# WL-BPF.net
KiCad netlist of a schematic drawn in Altium Designer
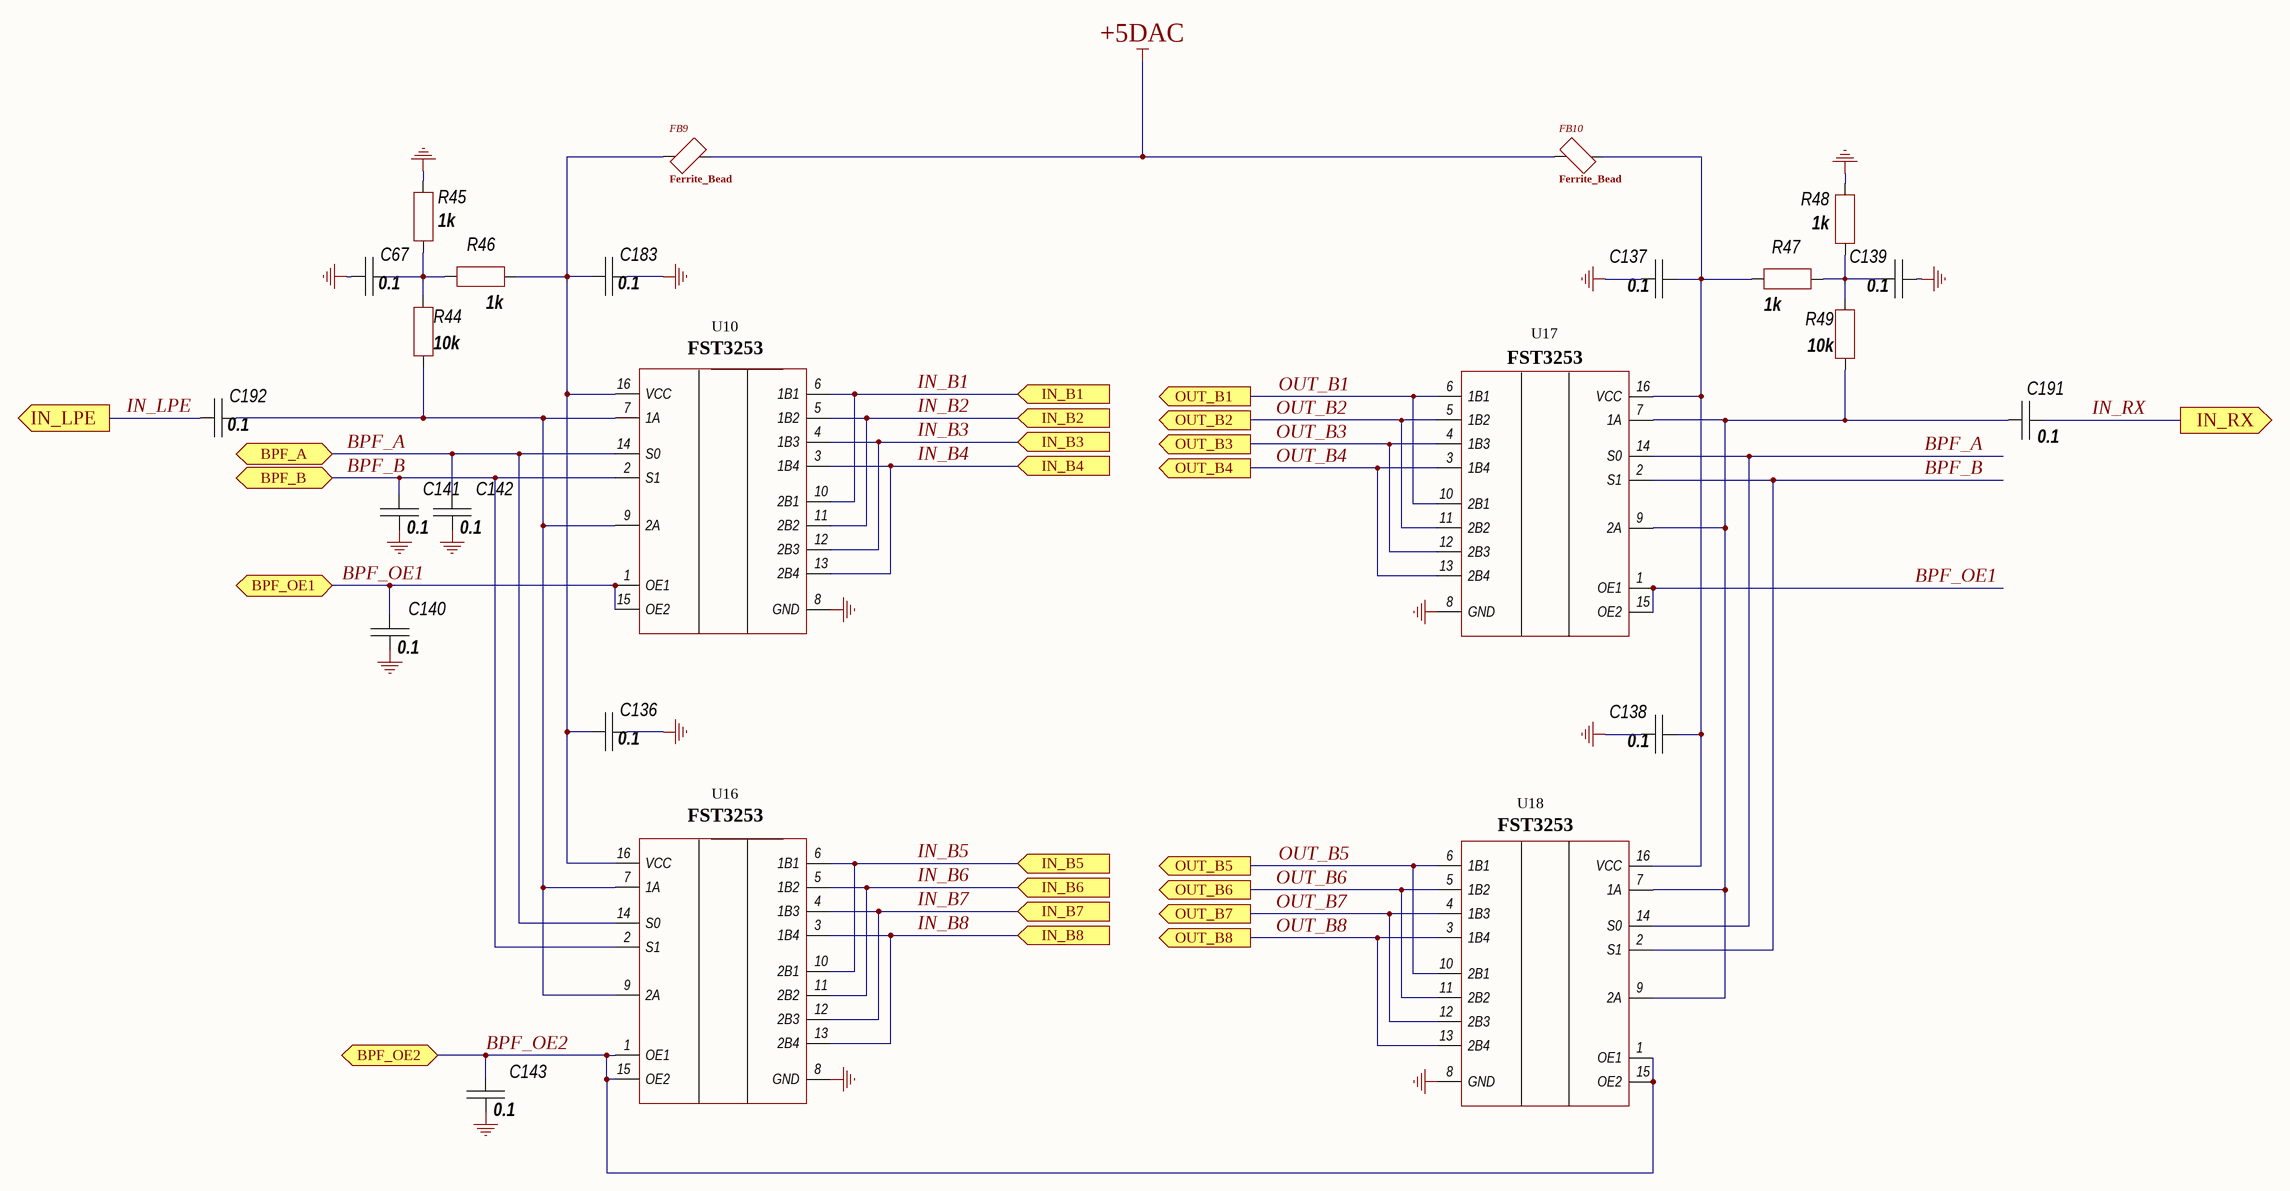
[diagram p0: WL-BPF.SchDoc]

(export (version "E")
  (design (tool "Eeschema 10.0.6"))
  (components
    (comp (ref "C67")
      (value "0.1")
      (footprint "standard:CH0805C")
      (libsource (lib "Discrete") (part "Capacitor"))
    )
    (comp (ref "C136")
      (value "0.1")
      (footprint "standard:CH0805C")
      (libsource (lib "Discrete") (part "Capacitor"))
    )
    (comp (ref "C137")
      (value "0.1")
      (footprint "standard:CH0805C")
      (libsource (lib "Discrete") (part "Capacitor"))
    )
    (comp (ref "C138")
      (value "0.1")
      (footprint "standard:CH0805C")
      (libsource (lib "Discrete") (part "Capacitor"))
    )
    (comp (ref "C139")
      (value "0.1")
      (footprint "standard:CH0805C")
      (libsource (lib "Discrete") (part "Capacitor"))
    )
    (comp (ref "C140")
      (value "0.1")
      (footprint "standard:CH0805C")
      (libsource (lib "Discrete") (part "Capacitor"))
    )
    (comp (ref "C141")
      (value "0.1")
      (footprint "standard:CH0805C")
      (libsource (lib "Discrete") (part "Capacitor"))
    )
    (comp (ref "C142")
      (value "0.1")
      (footprint "standard:CH0805C")
      (libsource (lib "Discrete") (part "Capacitor"))
    )
    (comp (ref "C143")
      (value "0.1")
      (footprint "standard:CH0805C")
      (libsource (lib "Discrete") (part "Capacitor"))
    )
    (comp (ref "C183")
      (value "0.1")
      (footprint "standard:CH0805C")
      (libsource (lib "Discrete") (part "Capacitor"))
    )
    (comp (ref "C191")
      (value "0.1")
      (footprint "standard:CH0805C")
      (libsource (lib "Discrete") (part "Capacitor"))
    )
    (comp (ref "C192")
      (value "0.1")
      (footprint "standard:CH0805C")
      (libsource (lib "Discrete") (part "Capacitor"))
    )
    (comp (ref "FB9") (value "Ferrite_Bead") (footprint "CH0805L") (libsource (lib "Discrete") (part "FB")))
    (comp (ref "FB10") (value "Ferrite_Bead") (footprint "CH0805L") (libsource (lib "Discrete") (part "FB")))
    (comp (ref "R44")
      (value "10k")
      (footprint "standard:CH0805R")
      (libsource (lib "Discrete") (part "Resistor"))
    )
    (comp (ref "R45") (value "1k") (footprint "standard:CH0805R") (libsource (lib "") (part "Resistor_2")))
    (comp (ref "R46") (value "1k") (footprint "standard:CH0805R") (libsource (lib "") (part "Resistor_1")))
    (comp (ref "R47")
      (value "1k")
      (footprint "standard:CH0805R")
      (libsource (lib "Discrete") (part "Resistor"))
    )
    (comp (ref "R48") (value "1k") (footprint "standard:CH0805R") (libsource (lib "") (part "Resistor_1")))
    (comp (ref "R49") (value "10k") (footprint "standard:CH0805R") (libsource (lib "") (part "Resistor_3")))
    (comp (ref "U10") (value "FST3253") (footprint "16-SSOP") (libsource (lib "Digital") (part "FST3253")))
    (comp (ref "U16") (value "FST3253") (footprint "16-SSOP") (libsource (lib "Digital") (part "FST3253")))
    (comp (ref "U17") (value "FST3253") (footprint "16-SSOP") (libsource (lib "") (part "FST3253_1")))
    (comp (ref "U18") (value "FST3253") (footprint "16-SSOP") (libsource (lib "") (part "FST3253_1")))
  )
  (nets
    (net (code "1") (name "+5DAC") (class "Default")
      (node (ref "FB10") (pin "2") (pinfunction "2_2") (pintype "passive"))
      (node (ref "FB9") (pin "2") (pinfunction "2_2") (pintype "passive"))
    )
    (net (code "2") (name "/BPF_A") (class "Default")
      (node (ref "C142") (pin "1") (pinfunction "1_1") (pintype "power_in"))
      (node (ref "U10") (pin "14") (pinfunction "S0_14") (pintype "passive"))
      (node (ref "U16") (pin "14") (pinfunction "S0_14") (pintype "passive"))
      (node (ref "U17") (pin "14") (pinfunction "S0_14") (pintype "passive"))
      (node (ref "U18") (pin "14") (pinfunction "S0_14") (pintype "passive"))
    )
    (net (code "3") (name "/BPF_B") (class "Default")
      (node (ref "C141") (pin "1") (pinfunction "1_1") (pintype "power_in"))
      (node (ref "U10") (pin "2") (pinfunction "S1_2") (pintype "passive"))
      (node (ref "U16") (pin "2") (pinfunction "S1_2") (pintype "passive"))
      (node (ref "U17") (pin "2") (pinfunction "S1_2") (pintype "passive"))
      (node (ref "U18") (pin "2") (pinfunction "S1_2") (pintype "passive"))
    )
    (net (code "4") (name "/BPF_OE1") (class "Default")
      (node (ref "C140") (pin "1") (pinfunction "1_1") (pintype "power_in"))
      (node (ref "U10") (pin "1") (pinfunction "OE1_1") (pintype "passive"))
      (node (ref "U10") (pin "15") (pinfunction "OE2_15") (pintype "passive"))
      (node (ref "U17") (pin "1") (pinfunction "OE1_1") (pintype "passive"))
      (node (ref "U17") (pin "15") (pinfunction "OE2_15") (pintype "passive"))
    )
    (net (code "5") (name "/BPF_OE2") (class "Default")
      (node (ref "C143") (pin "1") (pinfunction "1_1") (pintype "power_in"))
      (node (ref "U16") (pin "1") (pinfunction "OE1_1") (pintype "passive"))
      (node (ref "U16") (pin "15") (pinfunction "OE2_15") (pintype "passive"))
      (node (ref "U18") (pin "1") (pinfunction "OE1_1") (pintype "passive"))
      (node (ref "U18") (pin "15") (pinfunction "OE2_15") (pintype "passive"))
    )
    (net (code "6") (name "/IN_B1") (class "Default")
      (node (ref "U10") (pin "10") (pinfunction "2B1_10") (pintype "passive"))
      (node (ref "U10") (pin "6") (pinfunction "1B1_6") (pintype "passive"))
    )
    (net (code "7") (name "/IN_B2") (class "Default")
      (node (ref "U10") (pin "11") (pinfunction "2B2_11") (pintype "passive"))
      (node (ref "U10") (pin "5") (pinfunction "1B2_5") (pintype "passive"))
    )
    (net (code "8") (name "/IN_B3") (class "Default")
      (node (ref "U10") (pin "12") (pinfunction "2B3_12") (pintype "passive"))
      (node (ref "U10") (pin "4") (pinfunction "1B3_4") (pintype "passive"))
    )
    (net (code "9") (name "/IN_B4") (class "Default")
      (node (ref "U10") (pin "13") (pinfunction "2B4_13") (pintype "passive"))
      (node (ref "U10") (pin "3") (pinfunction "1B4_3") (pintype "passive"))
    )
    (net (code "10") (name "/IN_B5") (class "Default")
      (node (ref "U16") (pin "10") (pinfunction "2B1_10") (pintype "passive"))
      (node (ref "U16") (pin "6") (pinfunction "1B1_6") (pintype "passive"))
    )
    (net (code "11") (name "/IN_B6") (class "Default")
      (node (ref "U16") (pin "11") (pinfunction "2B2_11") (pintype "passive"))
      (node (ref "U16") (pin "5") (pinfunction "1B2_5") (pintype "passive"))
    )
    (net (code "12") (name "/IN_B7") (class "Default")
      (node (ref "U16") (pin "12") (pinfunction "2B3_12") (pintype "passive"))
      (node (ref "U16") (pin "4") (pinfunction "1B3_4") (pintype "passive"))
    )
    (net (code "13") (name "/IN_B8") (class "Default")
      (node (ref "U16") (pin "13") (pinfunction "2B4_13") (pintype "passive"))
      (node (ref "U16") (pin "3") (pinfunction "1B4_3") (pintype "passive"))
    )
    (net (code "14") (name "/IN_LPE") (class "Default")
      (node (ref "C192") (pin "1") (pinfunction "1_1") (pintype "power_in"))
    )
    (net (code "15") (name "/IN_RX") (class "Default")
      (node (ref "C191") (pin "1") (pinfunction "1_1") (pintype "power_in"))
    )
    (net (code "16") (name "/OUT_B1") (class "Default")
      (node (ref "U17") (pin "10") (pinfunction "2B1_10") (pintype "passive"))
      (node (ref "U17") (pin "6") (pinfunction "1B1_6") (pintype "passive"))
    )
    (net (code "17") (name "/OUT_B2") (class "Default")
      (node (ref "U17") (pin "11") (pinfunction "2B2_11") (pintype "passive"))
      (node (ref "U17") (pin "5") (pinfunction "1B2_5") (pintype "passive"))
    )
    (net (code "18") (name "/OUT_B3") (class "Default")
      (node (ref "U17") (pin "12") (pinfunction "2B3_12") (pintype "passive"))
      (node (ref "U17") (pin "4") (pinfunction "1B3_4") (pintype "passive"))
    )
    (net (code "19") (name "/OUT_B4") (class "Default")
      (node (ref "U17") (pin "13") (pinfunction "2B4_13") (pintype "passive"))
      (node (ref "U17") (pin "3") (pinfunction "1B4_3") (pintype "passive"))
    )
    (net (code "20") (name "/OUT_B5") (class "Default")
      (node (ref "U18") (pin "10") (pinfunction "2B1_10") (pintype "passive"))
      (node (ref "U18") (pin "6") (pinfunction "1B1_6") (pintype "passive"))
    )
    (net (code "21") (name "/OUT_B6") (class "Default")
      (node (ref "U18") (pin "11") (pinfunction "2B2_11") (pintype "passive"))
      (node (ref "U18") (pin "5") (pinfunction "1B2_5") (pintype "passive"))
    )
    (net (code "22") (name "/OUT_B7") (class "Default")
      (node (ref "U18") (pin "12") (pinfunction "2B3_12") (pintype "passive"))
      (node (ref "U18") (pin "4") (pinfunction "1B3_4") (pintype "passive"))
    )
    (net (code "23") (name "/OUT_B8") (class "Default")
      (node (ref "U18") (pin "13") (pinfunction "2B4_13") (pintype "passive"))
      (node (ref "U18") (pin "3") (pinfunction "1B4_3") (pintype "passive"))
    )
    (net (code "24") (name "GND") (class "Default")
      (node (ref "C136") (pin "2") (pinfunction "2_2") (pintype "power_in"))
      (node (ref "C137") (pin "2") (pinfunction "2_2") (pintype "power_in"))
      (node (ref "C138") (pin "2") (pinfunction "2_2") (pintype "power_in"))
      (node (ref "C139") (pin "1") (pinfunction "1_1") (pintype "power_in"))
      (node (ref "C140") (pin "2") (pinfunction "2_2") (pintype "power_in"))
      (node (ref "C141") (pin "2") (pinfunction "2_2") (pintype "power_in"))
      (node (ref "C142") (pin "2") (pinfunction "2_2") (pintype "power_in"))
      (node (ref "C143") (pin "2") (pinfunction "2_2") (pintype "power_in"))
      (node (ref "C183") (pin "2") (pinfunction "2_2") (pintype "power_in"))
      (node (ref "C67") (pin "1") (pinfunction "1_1") (pintype "power_in"))
      (node (ref "R45") (pin "1") (pinfunction "1_1") (pintype "passive"))
      (node (ref "R48") (pin "1") (pinfunction "1_1") (pintype "passive"))
      (node (ref "U10") (pin "8") (pinfunction "GND_8") (pintype "passive"))
      (node (ref "U16") (pin "8") (pinfunction "GND_8") (pintype "passive"))
      (node (ref "U17") (pin "8") (pinfunction "GND_8") (pintype "passive"))
      (node (ref "U18") (pin "8") (pinfunction "GND_8") (pintype "passive"))
    )
    (net (code "25") (name "Net-(C67-Pad2)") (class "Default")
      (node (ref "C67") (pin "2") (pinfunction "2_2") (pintype "power_in"))
      (node (ref "R44") (pin "2") (pinfunction "2_2") (pintype "passive"))
      (node (ref "R45") (pin "2") (pinfunction "2_2") (pintype "passive"))
      (node (ref "R46") (pin "2") (pinfunction "2_2") (pintype "passive"))
    )
    (net (code "26") (name "Net-(C139-Pad2)") (class "Default")
      (node (ref "C139") (pin "2") (pinfunction "2_2") (pintype "power_in"))
      (node (ref "R47") (pin "2") (pinfunction "2_2") (pintype "passive"))
      (node (ref "R48") (pin "2") (pinfunction "2_2") (pintype "passive"))
      (node (ref "R49") (pin "2") (pinfunction "2_2") (pintype "passive"))
    )
    (net (code "27") (name "Net-(U10-1A)") (class "Default")
      (node (ref "C192") (pin "2") (pinfunction "2_2") (pintype "power_in"))
      (node (ref "R44") (pin "1") (pinfunction "1_1") (pintype "passive"))
      (node (ref "U10") (pin "7") (pinfunction "1A_7") (pintype "passive"))
      (node (ref "U10") (pin "9") (pinfunction "2A_9") (pintype "passive"))
      (node (ref "U16") (pin "7") (pinfunction "1A_7") (pintype "passive"))
      (node (ref "U16") (pin "9") (pinfunction "2A_9") (pintype "passive"))
    )
    (net (code "28") (name "Net-(U10-VCC)") (class "Default")
      (node (ref "C136") (pin "1") (pinfunction "1_1") (pintype "power_in"))
      (node (ref "C183") (pin "1") (pinfunction "1_1") (pintype "power_in"))
      (node (ref "FB9") (pin "1") (pinfunction "1_1") (pintype "passive"))
      (node (ref "R46") (pin "1") (pinfunction "1_1") (pintype "passive"))
      (node (ref "U10") (pin "16") (pinfunction "VCC_16") (pintype "passive"))
      (node (ref "U16") (pin "16") (pinfunction "VCC_16") (pintype "passive"))
    )
    (net (code "29") (name "Net-(U17-1A)") (class "Default")
      (node (ref "C191") (pin "2") (pinfunction "2_2") (pintype "power_in"))
      (node (ref "R49") (pin "1") (pinfunction "1_1") (pintype "passive"))
      (node (ref "U17") (pin "7") (pinfunction "1A_7") (pintype "passive"))
      (node (ref "U17") (pin "9") (pinfunction "2A_9") (pintype "passive"))
      (node (ref "U18") (pin "7") (pinfunction "1A_7") (pintype "passive"))
      (node (ref "U18") (pin "9") (pinfunction "2A_9") (pintype "passive"))
    )
    (net (code "30") (name "Net-(U17-VCC)") (class "Default")
      (node (ref "C137") (pin "1") (pinfunction "1_1") (pintype "power_in"))
      (node (ref "C138") (pin "1") (pinfunction "1_1") (pintype "power_in"))
      (node (ref "FB10") (pin "1") (pinfunction "1_1") (pintype "passive"))
      (node (ref "R47") (pin "1") (pinfunction "1_1") (pintype "passive"))
      (node (ref "U17") (pin "16") (pinfunction "VCC_16") (pintype "passive"))
      (node (ref "U18") (pin "16") (pinfunction "VCC_16") (pintype "passive"))
    )
  )
)
